# Encoder_Fin_ARM_-_Encoder_MCU.net
KiCad netlist of a schematic drawn in Altium Designer
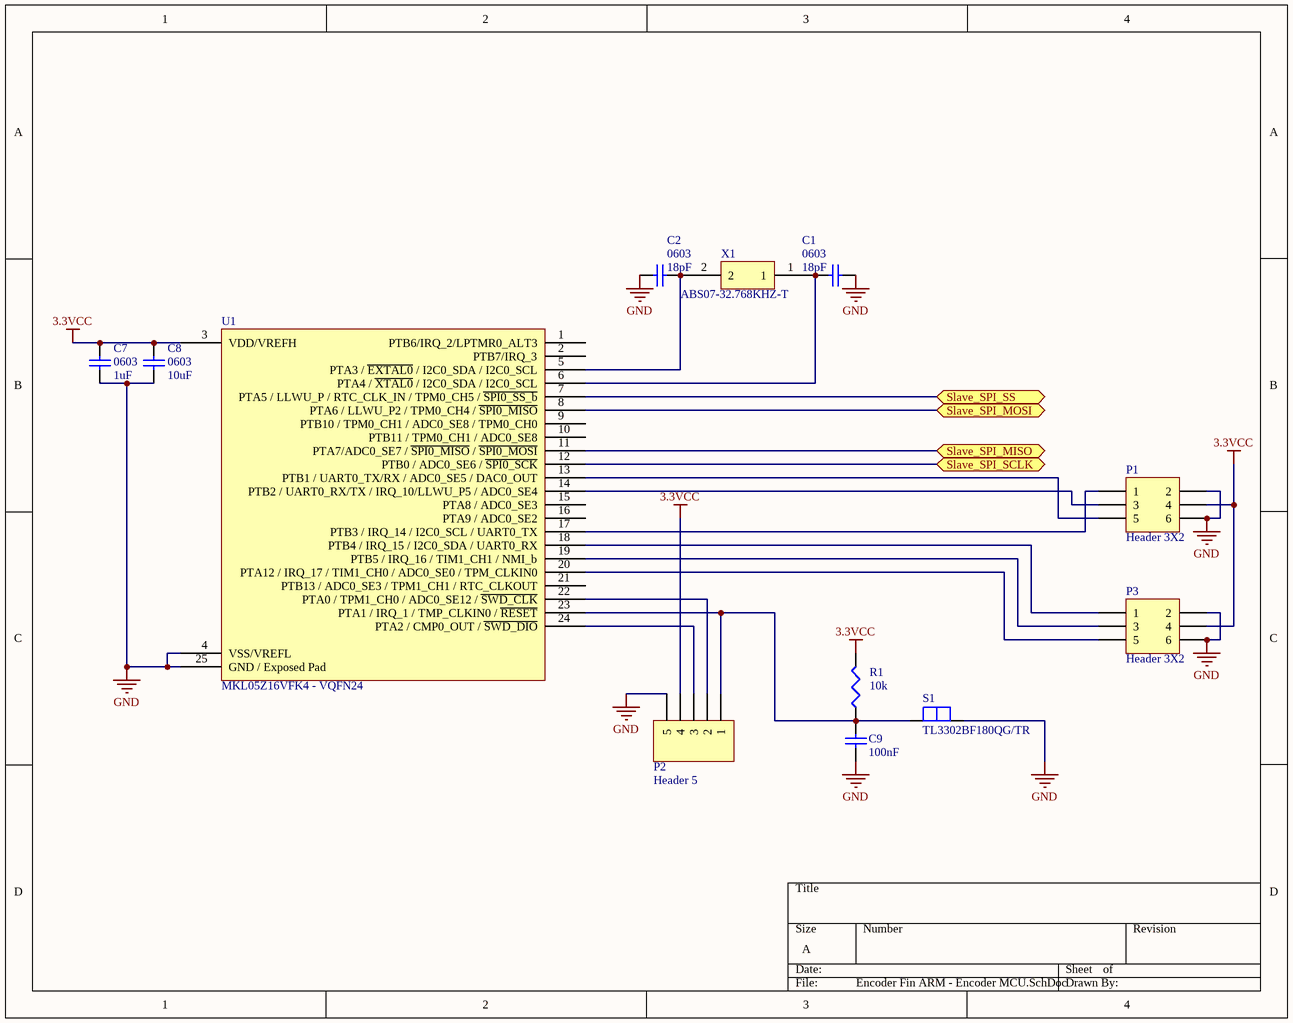
[diagram p0: Encoder Fin ARM - Encoder MCU.SchDoc]

(export (version "E")
  (design (tool "Eeschema 10.0.6"))
  (components
    (comp (ref "C1")
      (value "0603")
      (footprint "1608[0603]")
      (description "Capacitor (Semiconductor SIM Model)")
      (fields (field (name "ALTIUM_VALUE") "18pF") (field (name "PUBLISHER") "Altium Limited"))
      (libsource (lib "Miscellaneous Devices") (part "Cap Semi"))
    )
    (comp (ref "C2")
      (value "0603")
      (footprint "1608[0603]")
      (description "Capacitor (Semiconductor SIM Model)")
      (fields (field (name "ALTIUM_VALUE") "18pF") (field (name "PUBLISHER") "Altium Limited"))
      (libsource (lib "Miscellaneous Devices") (part "Cap Semi"))
    )
    (comp (ref "C7")
      (value "0603")
      (footprint "1608[0603]")
      (description "Capacitor (Semiconductor SIM Model)")
      (fields (field (name "ALTIUM_VALUE") "1uF") (field (name "PUBLISHER") "Altium Limited"))
      (libsource (lib "Miscellaneous Devices") (part "Cap Semi"))
    )
    (comp (ref "C8")
      (value "0603")
      (footprint "1608[0603]")
      (description "Capacitor (Semiconductor SIM Model)")
      (fields (field (name "ALTIUM_VALUE") "10uF") (field (name "PUBLISHER") "Altium Limited"))
      (libsource (lib "Miscellaneous Devices") (part "Cap Semi"))
    )
    (comp (ref "C9")
      (value "100nF")
      (footprint "1608[0603]")
      (description "Capacitor (Semiconductor SIM Model)")
      (fields (field (name "Comment") "Cap Semi") (field (name "PUBLISHER") "Altium Limited"))
      (libsource (lib "Miscellaneous Devices") (part "Cap Semi"))
    )
    (comp (ref "P1")
      (value "Header 3X2")
      (footprint "HDR2X3 Shrouded - Molex 0901301106")
      (description "Header, 3-Pin, Dual row")
      (fields (field (name "PUBLISHER") "Altium Limited"))
      (libsource (lib "Miscellaneous Connectors") (part "Header 3X2"))
    )
    (comp (ref "P2")
      (value "Header 5")
      (footprint "HDR1X5")
      (description "Header, 5-Pin")
      (fields (field (name "PUBLISHER") "Altium Limited"))
      (libsource (lib "Miscellaneous Connectors") (part "Header 5"))
    )
    (comp (ref "P3")
      (value "Header 3X2")
      (footprint "HDR2X3 Shrouded - Molex 0901301106")
      (description "Header, 3-Pin, Dual row")
      (fields (field (name "PUBLISHER") "Altium Limited"))
      (libsource (lib "Miscellaneous Connectors") (part "Header 3X2"))
    )
    (comp (ref "R1")
      (value "10k")
      (footprint "J1-0603")
      (description "Resistor")
      (fields (field (name "Comment") "Res3") (field (name "PUBLISHER") "Altium Limited"))
      (libsource (lib "Miscellaneous Devices") (part "Res3"))
    )
    (comp (ref "S1")
      (value "TL3302BF180QG/TR")
      (footprint "TL3302BF180QG/TR")
      (description "Tactile Switch Tiny")
      (libsource (lib "Encoder Fin") (part "TL3302BF180QG/TR"))
    )
    (comp (ref "U1")
      (value "MKL05Z16VFK4 - VQFN24")
      (footprint "98ASA00474D")
      (description "ARM Cortex M0+")
      (libsource (lib "Encoder Fin") (part "MKL05Z16VFK4 - 24 Pin VQFN"))
    )
    (comp (ref "X1")
      (value "ABS07-32.768KHZ-T")
      (footprint "ABS07-32.768KHZ-T")
      (description "ABS07-32.768KHZ-T RTC Crystal Oscillator")
      (libsource (lib "Adams Altium Library") (part "ABS07-32.768KHZ-T"))
    )
  )
  (nets
    (net (code "1") (name "/Slave_SPI_MISO") (class "Default")
      (node (ref "U1") (pin "11") (pinfunction "PTA7/ADC0_SE7_/_~{SPI0_MISO}_/_~{SPI0_MOSI}_11") (pintype "passive"))
    )
    (net (code "2") (name "/Slave_SPI_MOSI") (class "Default")
      (node (ref "U1") (pin "8") (pinfunction "PTA6_/_LLWU_P2_/_TPM0_CH4_/_~{SPI0_MISO}_8") (pintype "passive"))
    )
    (net (code "3") (name "/Slave_SPI_SCLK") (class "Default")
      (node (ref "U1") (pin "12") (pinfunction "PTB0_/_ADC0_SE6_/_~{SPI0_SCK}_12") (pintype "passive"))
    )
    (net (code "4") (name "/Slave_SPI_SS") (class "Default")
      (node (ref "U1") (pin "7") (pinfunction "PTA5_/_LLWU_P_/_RTC_CLK_IN_/_TPM0_CH5_/_~{SPI0_SS_b}_7") (pintype "passive"))
    )
    (net (code "5") (name "3.3VCC") (class "Default")
      (node (ref "C7") (pin "2") (pinfunction "2_2") (pintype "passive"))
      (node (ref "C8") (pin "2") (pinfunction "2_2") (pintype "passive"))
      (node (ref "P1") (pin "4") (pinfunction "4_4") (pintype "passive"))
      (node (ref "P2") (pin "4") (pinfunction "4_4") (pintype "passive"))
      (node (ref "P3") (pin "4") (pinfunction "4_4") (pintype "passive"))
      (node (ref "R1") (pin "2") (pinfunction "2_2") (pintype "passive"))
      (node (ref "U1") (pin "3") (pinfunction "VDD/VREFH_3") (pintype "passive"))
    )
    (net (code "6") (name "GND") (class "Default")
      (node (ref "C1") (pin "2") (pinfunction "2_2") (pintype "passive"))
      (node (ref "C2") (pin "2") (pinfunction "2_2") (pintype "passive"))
      (node (ref "C7") (pin "1") (pinfunction "1_1") (pintype "passive"))
      (node (ref "C8") (pin "1") (pinfunction "1_1") (pintype "passive"))
      (node (ref "C9") (pin "1") (pinfunction "1_1") (pintype "passive"))
      (node (ref "P1") (pin "2") (pinfunction "2_2") (pintype "passive"))
      (node (ref "P1") (pin "6") (pinfunction "6_6") (pintype "passive"))
      (node (ref "P2") (pin "5") (pinfunction "5_5") (pintype "passive"))
      (node (ref "P3") (pin "2") (pinfunction "2_2") (pintype "passive"))
      (node (ref "P3") (pin "6") (pinfunction "6_6") (pintype "passive"))
      (node (ref "S1") (pin "2") (pinfunction "2_2") (pintype "passive"))
      (node (ref "U1") (pin "25") (pinfunction "GND_/_Exposed_Pad_25") (pintype "passive"))
      (node (ref "U1") (pin "4") (pinfunction "VSS/VREFL_4") (pintype "passive"))
    )
    (net (code "7") (name "Net-(U1-PTA0_{slash}_TPM1_CH0_{slash}_ADC0_SE12_{slash}_~{SWD_CLK})") (class "Default")
      (node (ref "P2") (pin "2") (pinfunction "2_2") (pintype "passive"))
      (node (ref "U1") (pin "22") (pinfunction "PTA0_/_TPM1_CH0_/_ADC0_SE12_/_~{SWD_CLK}_22") (pintype "passive"))
    )
    (net (code "8") (name "Net-(U1-PTA1_{slash}_IRQ_1_{slash}_TMP_CLKIN0_{slash}_~{RESET})") (class "Default")
      (node (ref "C9") (pin "2") (pinfunction "2_2") (pintype "passive"))
      (node (ref "P2") (pin "1") (pinfunction "1_1") (pintype "passive"))
      (node (ref "R1") (pin "1") (pinfunction "1_1") (pintype "passive"))
      (node (ref "S1") (pin "1") (pinfunction "1_1") (pintype "passive"))
      (node (ref "U1") (pin "23") (pinfunction "PTA1_/_IRQ_1_/_TMP_CLKIN0_/_~{RESET}_23") (pintype "passive"))
    )
    (net (code "9") (name "Net-(U1-PTA2_{slash}_CMP0_OUT_{slash}_~{SWD_DIO})") (class "Default")
      (node (ref "P2") (pin "3") (pinfunction "3_3") (pintype "passive"))
      (node (ref "U1") (pin "24") (pinfunction "PTA2_/_CMP0_OUT_/_~{SWD_DIO}_24") (pintype "passive"))
    )
    (net (code "10") (name "Net-(U1-PTA3_{slash}_~{EXTAL0}_{slash}_I2C0_SDA_{slash}_I2C0_SCL)") (class "Default")
      (node (ref "C2") (pin "1") (pinfunction "1_1") (pintype "passive"))
      (node (ref "U1") (pin "5") (pinfunction "PTA3_/_~{EXTAL0}_/_I2C0_SDA_/_I2C0_SCL_5") (pintype "passive"))
      (node (ref "X1") (pin "2") (pinfunction "2_2") (pintype "passive"))
    )
    (net (code "11") (name "Net-(U1-PTA4_{slash}_~{XTAL0}_{slash}_I2C0_SDA_{slash}_I2C0_SCL)") (class "Default")
      (node (ref "C1") (pin "1") (pinfunction "1_1") (pintype "passive"))
      (node (ref "U1") (pin "6") (pinfunction "PTA4_/_~{XTAL0}_/_I2C0_SDA_/_I2C0_SCL_6") (pintype "passive"))
      (node (ref "X1") (pin "1") (pinfunction "1_1") (pintype "passive"))
    )
    (net (code "12") (name "Net-(U1-PTA12_{slash}_IRQ_17_{slash}_TIM1_CH0_{slash}_ADC0_SE0_{slash}_TPM_CLKIN0)") (class "Default")
      (node (ref "P3") (pin "5") (pinfunction "5_5") (pintype "passive"))
      (node (ref "U1") (pin "20") (pinfunction "PTA12_/_IRQ_17_/_TIM1_CH0_/_ADC0_SE0_/_TPM_CLKIN0_20") (pintype "passive"))
    )
    (net (code "13") (name "Net-(U1-PTB1_{slash}_UART0_TX{slash}RX_{slash}_ADC0_SE5_{slash}_DAC0_OUT)") (class "Default")
      (node (ref "P1") (pin "5") (pinfunction "5_5") (pintype "passive"))
      (node (ref "U1") (pin "13") (pinfunction "PTB1_/_UART0_TX/RX_/_ADC0_SE5_/_DAC0_OUT_13") (pintype "passive"))
    )
    (net (code "14") (name "Net-(U1-PTB2_{slash}_UART0_RX{slash}TX_{slash}_IRQ_10{slash}LLWU_P5_{slash}_ADC0_SE4)") (class "Default")
      (node (ref "P1") (pin "3") (pinfunction "3_3") (pintype "passive"))
      (node (ref "U1") (pin "14") (pinfunction "PTB2_/_UART0_RX/TX_/_IRQ_10/LLWU_P5_/_ADC0_SE4_14") (pintype "passive"))
    )
    (net (code "15") (name "Net-(U1-PTB3_{slash}_IRQ_14_{slash}_I2C0_SCL_{slash}_UART0_TX)") (class "Default")
      (node (ref "P1") (pin "1") (pinfunction "1_1") (pintype "passive"))
      (node (ref "U1") (pin "17") (pinfunction "PTB3_/_IRQ_14_/_I2C0_SCL_/_UART0_TX_17") (pintype "passive"))
    )
    (net (code "16") (name "Net-(U1-PTB4_{slash}_IRQ_15_{slash}_I2C0_SDA_{slash}_UART0_RX)") (class "Default")
      (node (ref "P3") (pin "1") (pinfunction "1_1") (pintype "passive"))
      (node (ref "U1") (pin "18") (pinfunction "PTB4_/_IRQ_15_/_I2C0_SDA_/_UART0_RX_18") (pintype "passive"))
    )
    (net (code "17") (name "Net-(U1-PTB5_{slash}_IRQ_16_{slash}_TIM1_CH1_{slash}_NMI_b)") (class "Default")
      (node (ref "P3") (pin "3") (pinfunction "3_3") (pintype "passive"))
      (node (ref "U1") (pin "19") (pinfunction "PTB5_/_IRQ_16_/_TIM1_CH1_/_NMI_b_19") (pintype "passive"))
    )
    (net (code "18") (name "unconnected-(U1-PTA8_{slash}_ADC0_SE3-Pad15)") (class "Default")
      (node (ref "U1") (pin "15") (pinfunction "PTA8_/_ADC0_SE3_15") (pintype "passive"))
    )
    (net (code "19") (name "unconnected-(U1-PTA9_{slash}_ADC0_SE2-Pad16)") (class "Default")
      (node (ref "U1") (pin "16") (pinfunction "PTA9_/_ADC0_SE2_16") (pintype "passive"))
    )
    (net (code "20") (name "unconnected-(U1-PTB6{slash}IRQ_2{slash}LPTMR0_ALT3-Pad1)") (class "Default")
      (node (ref "U1") (pin "1") (pinfunction "PTB6/IRQ_2/LPTMR0_ALT3_1") (pintype "passive"))
    )
    (net (code "21") (name "unconnected-(U1-PTB7{slash}IRQ_3-Pad2)") (class "Default")
      (node (ref "U1") (pin "2") (pinfunction "PTB7/IRQ_3_2") (pintype "passive"))
    )
    (net (code "22") (name "unconnected-(U1-PTB10_{slash}_TPM0_CH1_{slash}_ADC0_SE8_{slash}_TPM0_CH0-Pad9)") (class "Default")
      (node (ref "U1") (pin "9") (pinfunction "PTB10_/_TPM0_CH1_/_ADC0_SE8_/_TPM0_CH0_9") (pintype "passive"))
    )
    (net (code "23") (name "unconnected-(U1-PTB11_{slash}_TPM0_CH1_{slash}_ADC0_SE8-Pad10)") (class "Default")
      (node (ref "U1") (pin "10") (pinfunction "PTB11_/_TPM0_CH1_/_ADC0_SE8_10") (pintype "passive"))
    )
    (net (code "24") (name "unconnected-(U1-PTB13_{slash}_ADC0_SE3_{slash}_TPM1_CH1_{slash}_RTC_CLKOUT-Pad21)") (class "Default")
      (node (ref "U1") (pin "21") (pinfunction "PTB13_/_ADC0_SE3_/_TPM1_CH1_/_RTC_CLKOUT_21") (pintype "passive"))
    )
  )
)
